# RS232_Interface.net
KiCad netlist of a schematic drawn in Altium Designer
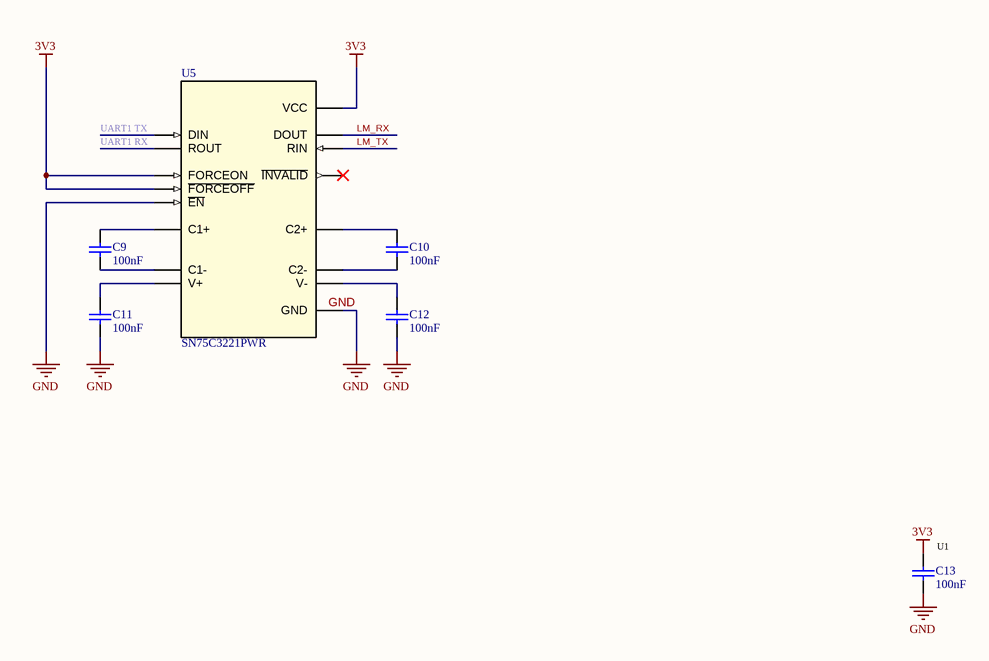
[diagram p0: RS232 Interface.SchDoc]

(export (version "E")
  (design (tool "Eeschema 10.0.6"))
  (components
    (comp (ref "C9")
      (value "100nF")
      (footprint "FP-GRM188-0_1-e0_2_0_5-IPC_B")
      (description "0.1µF ±10% 100V Ceramic Capacitor X7R 0603 (1608 Metric)")
      (fields (field (name "VOLTAGE") "100V") (field (name "TOLERANCE") "10%"))
      (libsource (lib "Sainsbury Wellcome Centre") (part "Cap"))
    )
    (comp (ref "C10")
      (value "100nF")
      (footprint "FP-GRM188-0_1-e0_2_0_5-IPC_B")
      (description "0.1µF ±10% 100V Ceramic Capacitor X7R 0603 (1608 Metric)")
      (fields (field (name "VOLTAGE") "100V") (field (name "TOLERANCE") "10%"))
      (libsource (lib "Sainsbury Wellcome Centre") (part "Cap"))
    )
    (comp (ref "C11")
      (value "100nF")
      (footprint "FP-GRM188-0_1-e0_2_0_5-IPC_B")
      (description "0.1µF ±10% 100V Ceramic Capacitor X7R 0603 (1608 Metric)")
      (fields (field (name "VOLTAGE") "100V") (field (name "TOLERANCE") "10%"))
      (libsource (lib "Sainsbury Wellcome Centre") (part "Cap"))
    )
    (comp (ref "C12")
      (value "100nF")
      (footprint "FP-GRM188-0_1-e0_2_0_5-IPC_B")
      (description "0.1µF ±10% 100V Ceramic Capacitor X7R 0603 (1608 Metric)")
      (fields (field (name "VOLTAGE") "100V") (field (name "TOLERANCE") "10%"))
      (libsource (lib "Sainsbury Wellcome Centre") (part "Cap"))
    )
    (comp (ref "C13")
      (value "100nF")
      (footprint "FP-GRM188-0_1-e0_2_0_5-IPC_B")
      (description "0.1µF ±10% 100V Ceramic Capacitor X7R 0603 (1608 Metric)")
      (fields (field (name "VOLTAGE") "100V") (field (name "TOLERANCE") "10%"))
      (libsource (lib "Sainsbury Wellcome Centre") (part "Cap"))
    )
    (comp (ref "U5")
      (value "SN75C3221PWR")
      (footprint "PW0016A_N")
      (description "IC RS232 DRVR/RCVR 1-CH 16-TSSOP")
      (libsource (lib "Sainsbury Wellcome Centre") (part "TI-SN75C3221-TSSOP_PW-16"))
    )
  )
  (nets
    (net (code "1") (name "/LM_RX") (class "Default")
      (node (ref "U5") (pin "13") (pinfunction "DOUT_13") (pintype "tri_state"))
    )
    (net (code "2") (name "/LM_TX") (class "Default")
      (node (ref "U5") (pin "8") (pinfunction "RIN_8") (pintype "input"))
    )
    (net (code "3") (name "/UART1 RX") (class "Default")
      (node (ref "U5") (pin "9") (pinfunction "ROUT_9") (pintype "tri_state"))
    )
    (net (code "4") (name "/UART1 TX") (class "Default")
      (node (ref "U5") (pin "11") (pinfunction "DIN_11") (pintype "input"))
    )
    (net (code "5") (name "3V3") (class "Default")
      (node (ref "C13") (pin "2") (pinfunction "2_2") (pintype "passive"))
      (node (ref "U5") (pin "12") (pinfunction "FORCEON_12") (pintype "input"))
      (node (ref "U5") (pin "15") (pinfunction "VCC_15") (pintype "power_in"))
      (node (ref "U5") (pin "16") (pinfunction "~{FORCEOFF}_16") (pintype "input"))
    )
    (net (code "6") (name "GND") (class "Default")
      (node (ref "C11") (pin "1") (pinfunction "1_1") (pintype "passive"))
      (node (ref "C12") (pin "1") (pinfunction "1_1") (pintype "passive"))
      (node (ref "C13") (pin "1") (pinfunction "1_1") (pintype "passive"))
      (node (ref "U5") (pin "1") (pinfunction "~{EN}_1") (pintype "input"))
      (node (ref "U5") (pin "14") (pinfunction "GND_14") (pintype "power_in"))
    )
    (net (code "7") (name "Net-(U5-C1+)") (class "Default")
      (node (ref "C9") (pin "2") (pinfunction "2_2") (pintype "passive"))
      (node (ref "U5") (pin "2") (pinfunction "C1+_2") (pintype "passive"))
    )
    (net (code "8") (name "Net-(U5-C1-)") (class "Default")
      (node (ref "C9") (pin "1") (pinfunction "1_1") (pintype "passive"))
      (node (ref "U5") (pin "4") (pinfunction "C1-_4") (pintype "passive"))
    )
    (net (code "9") (name "Net-(U5-C2+)") (class "Default")
      (node (ref "C10") (pin "2") (pinfunction "2_2") (pintype "passive"))
      (node (ref "U5") (pin "5") (pinfunction "C2+_5") (pintype "passive"))
    )
    (net (code "10") (name "Net-(U5-C2-)") (class "Default")
      (node (ref "C10") (pin "1") (pinfunction "1_1") (pintype "passive"))
      (node (ref "U5") (pin "6") (pinfunction "C2-_6") (pintype "passive"))
    )
    (net (code "11") (name "Net-(U5-V+)") (class "Default")
      (node (ref "C11") (pin "2") (pinfunction "2_2") (pintype "passive"))
      (node (ref "U5") (pin "3") (pinfunction "V+_3") (pintype "power_in"))
    )
    (net (code "12") (name "Net-(U5-V-)") (class "Default")
      (node (ref "C12") (pin "2") (pinfunction "2_2") (pintype "passive"))
      (node (ref "U5") (pin "7") (pinfunction "V-_7") (pintype "power_in"))
    )
    (net (code "13") (name "unconnected-(U5-~{INVALID}-Pad10)") (class "Default")
      (node (ref "U5") (pin "10") (pinfunction "~{INVALID}_10") (pintype "output+no_connect"))
    )
  )
)
